# Sheet1.net
KiCad netlist of a schematic drawn in Altium Designer
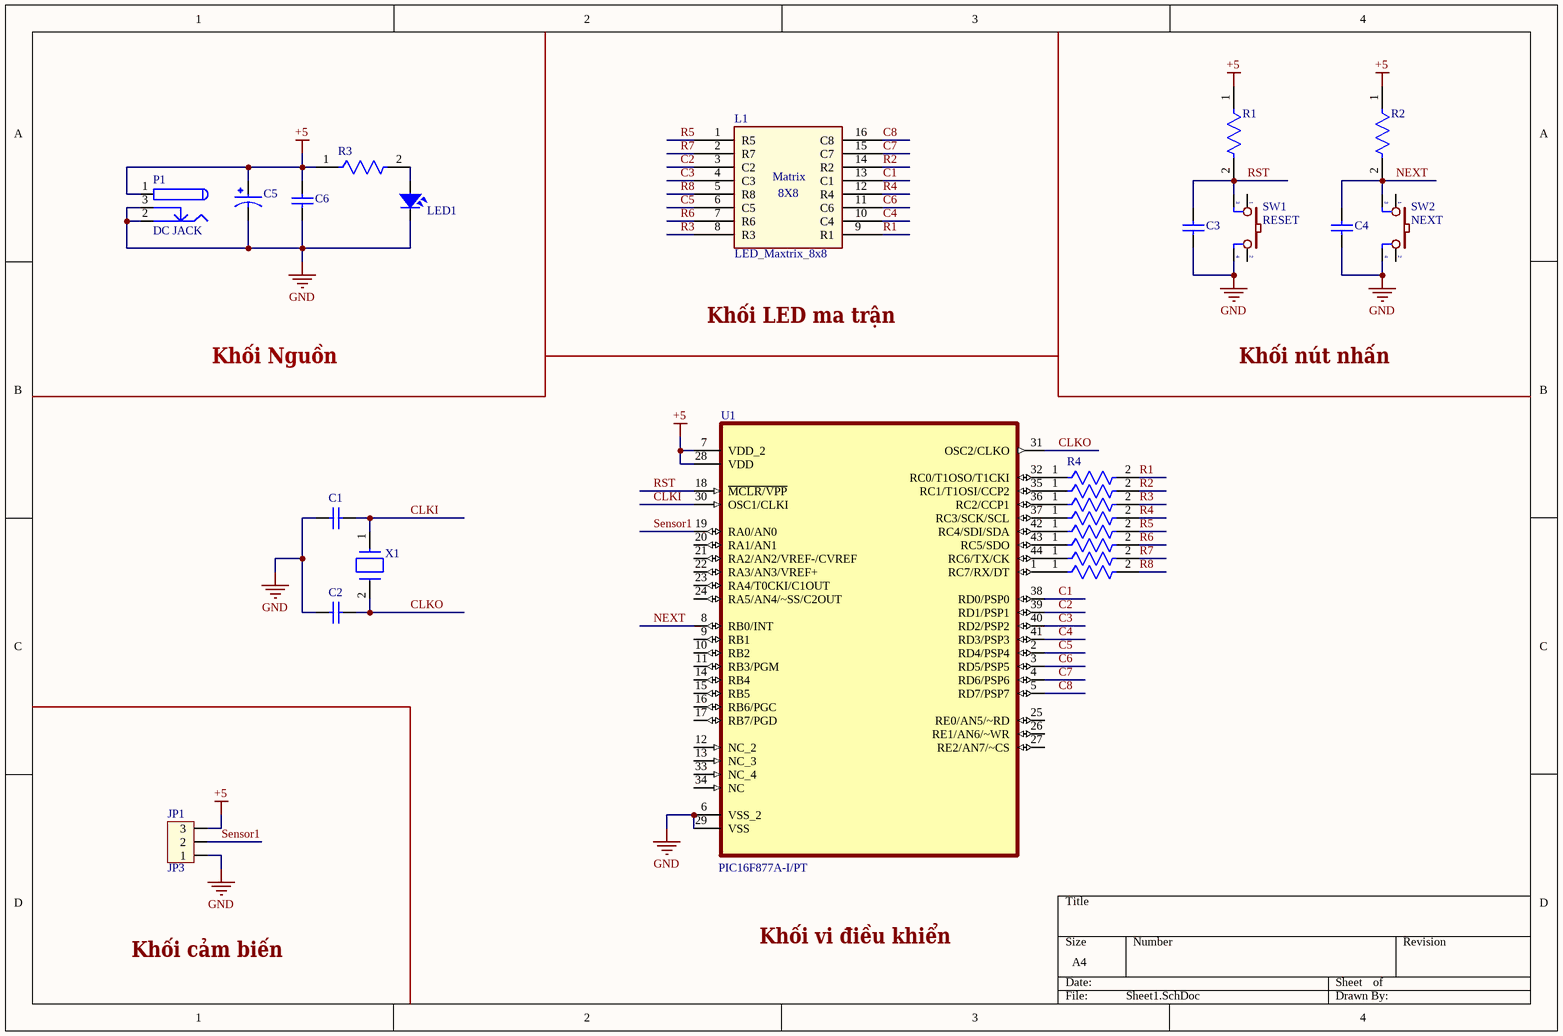
[diagram p0: Sheet1.SchDoc]

(export (version "E")
  (design (tool "Eeschema 10.0.6"))
  (components
    (comp (ref "C1")
      (value "22p")
      (footprint "CAPC2013X94X50LL25T25")
      (description "Cap Ceramic 0.1uF 100V X7R 10% SMD 0805 125°C Embossed T/R")
      (fields
        (field (name "MANUFACTURER") "Kyocera AVX")
        (field (name "MANUFACTURER PART NUMBER") "LD051C104KAB2A")
      )
      (libsource (lib "Lib_BookTS") (part "LD051C104KAB2A"))
    )
    (comp (ref "C2")
      (value "22p")
      (footprint "CAPC2013X94X50LL25T25")
      (description "Cap Ceramic 0.1uF 100V X7R 10% SMD 0805 125°C Embossed T/R")
      (fields
        (field (name "MANUFACTURER") "Kyocera AVX")
        (field (name "MANUFACTURER PART NUMBER") "LD051C104KAB2A")
      )
      (libsource (lib "Lib_BookTS") (part "LD051C104KAB2A"))
    )
    (comp (ref "C3")
      (value "0.1uF")
      (footprint "CAPC2013X94X50LL25T25")
      (description "Cap Ceramic 0.1uF 100V X7R 10% SMD 0805 125°C Embossed T/R")
      (fields
        (field (name "MANUFACTURER") "Kyocera AVX")
        (field (name "MANUFACTURER PART NUMBER") "LD051C104KAB2A")
      )
      (libsource (lib "Lib_BookTS") (part "LD051C104KAB2A"))
    )
    (comp (ref "C4")
      (value "0.1uF")
      (footprint "CAPC2013X94X50LL25T25")
      (description "Cap Ceramic 0.1uF 100V X7R 10% SMD 0805 125°C Embossed T/R")
      (fields
        (field (name "MANUFACTURER") "Kyocera AVX")
        (field (name "MANUFACTURER PART NUMBER") "LD051C104KAB2A")
      )
      (libsource (lib "Lib_BookTS") (part "LD051C104KAB2A"))
    )
    (comp (ref "C5")
      (value "EEE-FK1H101GP")
      (footprint "FP-FKF-MFG")
      (description "Cap Aluminum 100uF 50V 20% (8 X 10.2mm) SMD 350mA 5000 hr 105°C T/R")
      (fields (field (name "MANUFACTURER") "Panasonic") (field (name "TOLERANCE") "20%"))
      (libsource (lib "Lib_BookTS") (part "EEE-FK1H101GP"))
    )
    (comp (ref "C6")
      (value "0.1uF")
      (footprint "CAPC2013X94X50LL25T25")
      (description "Cap Ceramic 0.1uF 100V X7R 10% SMD 0805 125°C Embossed T/R")
      (fields
        (field (name "MANUFACTURER") "Kyocera AVX")
        (field (name "MANUFACTURER PART NUMBER") "LD051C104KAB2A")
      )
      (libsource (lib "Lib_BookTS") (part "LD051C104KAB2A"))
    )
    (comp (ref "JP1")
      (value "JP3")
      (footprint "CON3")
      (description "Connector 3")
      (libsource (lib "Lib_BookTS") (part "Con3"))
    )
    (comp (ref "L1")
      (value "LED_Maxtrix_8x8")
      (footprint "LED_Matrix_8x8")
      (libsource (lib "Lib_BookTS") (part "LED_Maxtrix_8x8"))
    )
    (comp (ref "LED1")
      (value "LED SMD")
      (footprint "SM-LED-0805-Green")
      (libsource (lib "Lib_BookTS") (part "LED-SMD-0805"))
    )
    (comp (ref "P1")
      (value "DC JACK")
      (footprint "DC5.5/2.1")
      (description "Low Voltage Power Supply Connector")
      (libsource (lib "Lib_BookTS") (part "DC5.5/2.1"))
    )
    (comp (ref "R1")
      (value "10k")
      (footprint "FP-CR0805-MFG")
      (description "Res Thick Film 0805 330 Ohm 5% 1/8W ±200ppm/°C Molded SMD SMD Paper Tape on Plastic Reel")
      (fields
        (field (name "MANUFACTURER") "Bourns")
        (field (name "MANUFACTURER PART NUMBER") "CR0805-JW-331ELF")
      )
      (libsource (lib "Lib_BookTS") (part "CR0805-JW-331ELF"))
    )
    (comp (ref "R2")
      (value "10k")
      (footprint "FP-CR0805-MFG")
      (description "Res Thick Film 0805 330 Ohm 5% 1/8W ±200ppm/°C Molded SMD SMD Paper Tape on Plastic Reel")
      (fields
        (field (name "MANUFACTURER") "Bourns")
        (field (name "MANUFACTURER PART NUMBER") "CR0805-JW-331ELF")
      )
      (libsource (lib "Lib_BookTS") (part "CR0805-JW-331ELF"))
    )
    (comp (ref "R3")
      (value "470R")
      (footprint "FP-CR0805-IPC_A")
      (description "Res Thick Film 0805 330 Ohm 5% 1/8W ±200ppm/°C Molded SMD SMD Paper Tape on Plastic Reel")
      (fields
        (field (name "MANUFACTURER") "Bourns")
        (field (name "MANUFACTURER PART NUMBER") "CR0805-JW-331ELF")
      )
      (libsource (lib "Lib_BookTS") (part "CR0805-JW-331ELF"))
    )
    (comp (ref "R4")
      (value "330R")
      (footprint "FP-CR0805-IPC_A")
      (description "Res Thick Film 0805 330 Ohm 5% 1/8W ±200ppm/°C Molded SMD SMD Paper Tape on Plastic Reel")
      (fields
        (field (name "MANUFACTURER") "Bourns")
        (field (name "MANUFACTURER PART NUMBER") "CR0805-JW-331ELF")
      )
      (libsource (lib "Lib_BookTS") (part "CR0805-JW-331ELF"))
    )
    (comp (ref "R5")
      (value "330R")
      (footprint "FP-CR0805-IPC_A")
      (description "Res Thick Film 0805 330 Ohm 5% 1/8W ±200ppm/°C Molded SMD SMD Paper Tape on Plastic Reel")
      (fields
        (field (name "MANUFACTURER") "Bourns")
        (field (name "MANUFACTURER PART NUMBER") "CR0805-JW-331ELF")
      )
      (libsource (lib "Lib_BookTS") (part "CR0805-JW-331ELF"))
    )
    (comp (ref "R6")
      (value "330R")
      (footprint "FP-CR0805-IPC_A")
      (description "Res Thick Film 0805 330 Ohm 5% 1/8W ±200ppm/°C Molded SMD SMD Paper Tape on Plastic Reel")
      (fields
        (field (name "MANUFACTURER") "Bourns")
        (field (name "MANUFACTURER PART NUMBER") "CR0805-JW-331ELF")
      )
      (libsource (lib "Lib_BookTS") (part "CR0805-JW-331ELF"))
    )
    (comp (ref "R7")
      (value "330R")
      (footprint "FP-CR0805-IPC_A")
      (description "Res Thick Film 0805 330 Ohm 5% 1/8W ±200ppm/°C Molded SMD SMD Paper Tape on Plastic Reel")
      (fields
        (field (name "MANUFACTURER") "Bourns")
        (field (name "MANUFACTURER PART NUMBER") "CR0805-JW-331ELF")
      )
      (libsource (lib "Lib_BookTS") (part "CR0805-JW-331ELF"))
    )
    (comp (ref "R8")
      (value "330R")
      (footprint "FP-CR0805-IPC_A")
      (description "Res Thick Film 0805 330 Ohm 5% 1/8W ±200ppm/°C Molded SMD SMD Paper Tape on Plastic Reel")
      (fields
        (field (name "MANUFACTURER") "Bourns")
        (field (name "MANUFACTURER PART NUMBER") "CR0805-JW-331ELF")
      )
      (libsource (lib "Lib_BookTS") (part "CR0805-JW-331ELF"))
    )
    (comp (ref "R9")
      (value "330R")
      (footprint "FP-CR0805-IPC_A")
      (description "Res Thick Film 0805 330 Ohm 5% 1/8W ±200ppm/°C Molded SMD SMD Paper Tape on Plastic Reel")
      (fields
        (field (name "MANUFACTURER") "Bourns")
        (field (name "MANUFACTURER PART NUMBER") "CR0805-JW-331ELF")
      )
      (libsource (lib "Lib_BookTS") (part "CR0805-JW-331ELF"))
    )
    (comp (ref "R10")
      (value "330R")
      (footprint "FP-CR0805-IPC_A")
      (description "Res Thick Film 0805 330 Ohm 5% 1/8W ±200ppm/°C Molded SMD SMD Paper Tape on Plastic Reel")
      (fields
        (field (name "MANUFACTURER") "Bourns")
        (field (name "MANUFACTURER PART NUMBER") "CR0805-JW-331ELF")
      )
      (libsource (lib "Lib_BookTS") (part "CR0805-JW-331ELF"))
    )
    (comp (ref "R11")
      (value "330R")
      (footprint "FP-CR0805-IPC_A")
      (description "Res Thick Film 0805 330 Ohm 5% 1/8W ±200ppm/°C Molded SMD SMD Paper Tape on Plastic Reel")
      (fields
        (field (name "MANUFACTURER") "Bourns")
        (field (name "MANUFACTURER PART NUMBER") "CR0805-JW-331ELF")
      )
      (libsource (lib "Lib_BookTS") (part "CR0805-JW-331ELF"))
    )
    (comp (ref "SW1")
      (value "RESET")
      (footprint "SW4")
      (description "Switch button 4 pin")
      (libsource (lib "Lib_BookTS") (part "SW4-1"))
    )
    (comp (ref "SW2")
      (value "NEXT")
      (footprint "SW4")
      (description "Switch button 4 pin")
      (libsource (lib "Lib_BookTS") (part "SW4-1"))
    )
    (comp (ref "U1")
      (value "PIC16F877A-I/PT")
      (footprint "TQFP-44")
      (description "PIC16F877A Microcontroller IC 8-Bit 20MHz 14KB _8K x 14_ FLASH 44-TQFP _10x10_")
      (fields (field (name "MF") "Microchip"))
      (libsource (lib "Lib_BookTS") (part "PIC16F877A-I/PT"))
    )
    (comp (ref "X1")
      (value "16MHz")
      (footprint "FP-ABM7-MFG")
      (description "Crystal 16MHz ±30ppm (Tol) ±50ppm (Stability) 18pF FUND 50Ohm 2-Pin Mini-CSMD T/R")
      (fields
        (field (name "MANUFACTURER") "Abracon")
        (field (name "MANUFACTURER PART NUMBER") "ABM7-16.000MHZ-4-T")
      )
      (libsource (lib "Lib_BookTS") (part "ABM7-16.000MHZ-4-T"))
    )
  )
  (nets
    (net (code "1") (name "+5") (class "Default")
      (node (ref "C5") (pin "1") (pinfunction "1_1") (pintype "passive"))
      (node (ref "C6") (pin "2") (pinfunction "2_2") (pintype "passive"))
      (node (ref "JP1") (pin "3") (pinfunction "3_3") (pintype "passive"))
      (node (ref "P1") (pin "1") (pinfunction "1_1") (pintype "power_in"))
      (node (ref "R1") (pin "1") (pinfunction "1_1") (pintype "passive"))
      (node (ref "R2") (pin "1") (pinfunction "1_1") (pintype "passive"))
      (node (ref "R3") (pin "1") (pinfunction "1_1") (pintype "passive"))
      (node (ref "U1") (pin "28") (pinfunction "VDD_28") (pintype "power_in"))
      (node (ref "U1") (pin "7") (pinfunction "VDD_2_7") (pintype "power_in"))
    )
    (net (code "2") (name "/C1") (class "Default")
      (node (ref "L1") (pin "13") (pinfunction "C1_13") (pintype "passive"))
      (node (ref "U1") (pin "38") (pinfunction "RD0/PSP0_38") (pintype "bidirectional"))
    )
    (net (code "3") (name "/C2") (class "Default")
      (node (ref "L1") (pin "3") (pinfunction "C2_3") (pintype "passive"))
      (node (ref "U1") (pin "39") (pinfunction "RD1/PSP1_39") (pintype "bidirectional"))
    )
    (net (code "4") (name "/C3") (class "Default")
      (node (ref "L1") (pin "4") (pinfunction "C3_4") (pintype "passive"))
      (node (ref "U1") (pin "40") (pinfunction "RD2/PSP2_40") (pintype "bidirectional"))
    )
    (net (code "5") (name "/C4") (class "Default")
      (node (ref "L1") (pin "10") (pinfunction "C4_10") (pintype "passive"))
      (node (ref "U1") (pin "41") (pinfunction "RD3/PSP3_41") (pintype "bidirectional"))
    )
    (net (code "6") (name "/C5") (class "Default")
      (node (ref "L1") (pin "6") (pinfunction "C5_6") (pintype "passive"))
      (node (ref "U1") (pin "2") (pinfunction "RD4/PSP4_2") (pintype "bidirectional"))
    )
    (net (code "7") (name "/C6") (class "Default")
      (node (ref "L1") (pin "11") (pinfunction "C6_11") (pintype "passive"))
      (node (ref "U1") (pin "3") (pinfunction "RD5/PSP5_3") (pintype "bidirectional"))
    )
    (net (code "8") (name "/C7") (class "Default")
      (node (ref "L1") (pin "15") (pinfunction "C7_15") (pintype "passive"))
      (node (ref "U1") (pin "4") (pinfunction "RD6/PSP6_4") (pintype "bidirectional"))
    )
    (net (code "9") (name "/C8") (class "Default")
      (node (ref "L1") (pin "16") (pinfunction "C8_16") (pintype "passive"))
      (node (ref "U1") (pin "5") (pinfunction "RD7/PSP7_5") (pintype "bidirectional"))
    )
    (net (code "10") (name "/CLKI") (class "Default")
      (node (ref "C1") (pin "2") (pinfunction "2_2") (pintype "passive"))
      (node (ref "U1") (pin "30") (pinfunction "OSC1/CLKI_30") (pintype "input"))
      (node (ref "X1") (pin "1") (pinfunction "1_1") (pintype "passive"))
    )
    (net (code "11") (name "/CLKO") (class "Default")
      (node (ref "C2") (pin "2") (pinfunction "2_2") (pintype "passive"))
      (node (ref "U1") (pin "31") (pinfunction "OSC2/CLKO_31") (pintype "output"))
      (node (ref "X1") (pin "2") (pinfunction "2_2") (pintype "passive"))
    )
    (net (code "16") (name "/NEXT") (class "Default")
      (node (ref "C4") (pin "2") (pinfunction "2_2") (pintype "passive"))
      (node (ref "R2") (pin "2") (pinfunction "2_2") (pintype "passive"))
      (node (ref "SW2") (pin "3") (pinfunction "3_3") (pintype "passive"))
      (node (ref "U1") (pin "8") (pinfunction "RB0/INT_8") (pintype "bidirectional"))
    )
    (net (code "17") (name "/R1") (class "Default")
      (node (ref "L1") (pin "9") (pinfunction "R1_9") (pintype "passive"))
      (node (ref "R4") (pin "2") (pinfunction "2_2") (pintype "passive"))
    )
    (net (code "18") (name "/R2") (class "Default")
      (node (ref "L1") (pin "14") (pinfunction "R2_14") (pintype "passive"))
      (node (ref "R5") (pin "2") (pinfunction "2_2") (pintype "passive"))
    )
    (net (code "19") (name "/R3") (class "Default")
      (node (ref "L1") (pin "8") (pinfunction "R3_8") (pintype "passive"))
      (node (ref "R6") (pin "2") (pinfunction "2_2") (pintype "passive"))
    )
    (net (code "20") (name "/R4") (class "Default")
      (node (ref "L1") (pin "12") (pinfunction "R4_12") (pintype "passive"))
      (node (ref "R7") (pin "2") (pinfunction "2_2") (pintype "passive"))
    )
    (net (code "21") (name "/R5") (class "Default")
      (node (ref "L1") (pin "1") (pinfunction "R5_1") (pintype "passive"))
      (node (ref "R8") (pin "2") (pinfunction "2_2") (pintype "passive"))
    )
    (net (code "22") (name "/R6") (class "Default")
      (node (ref "L1") (pin "7") (pinfunction "R6_7") (pintype "passive"))
      (node (ref "R9") (pin "2") (pinfunction "2_2") (pintype "passive"))
    )
    (net (code "23") (name "/R7") (class "Default")
      (node (ref "L1") (pin "2") (pinfunction "R7_2") (pintype "passive"))
      (node (ref "R10") (pin "2") (pinfunction "2_2") (pintype "passive"))
    )
    (net (code "24") (name "/R8") (class "Default")
      (node (ref "L1") (pin "5") (pinfunction "R8_5") (pintype "passive"))
      (node (ref "R11") (pin "2") (pinfunction "2_2") (pintype "passive"))
    )
    (net (code "25") (name "/RST") (class "Default")
      (node (ref "C3") (pin "2") (pinfunction "2_2") (pintype "passive"))
      (node (ref "R1") (pin "2") (pinfunction "2_2") (pintype "passive"))
      (node (ref "SW1") (pin "3") (pinfunction "3_3") (pintype "passive"))
      (node (ref "U1") (pin "18") (pinfunction "~{MCLR/VPP}_18") (pintype "input"))
    )
    (net (code "26") (name "/Sensor1") (class "Default")
      (node (ref "JP1") (pin "2") (pinfunction "2_2") (pintype "passive"))
      (node (ref "U1") (pin "19") (pinfunction "RA0/AN0_19") (pintype "bidirectional"))
    )
    (net (code "27") (name "GND") (class "Default")
      (node (ref "C1") (pin "1") (pinfunction "1_1") (pintype "passive"))
      (node (ref "C2") (pin "1") (pinfunction "1_1") (pintype "passive"))
      (node (ref "C3") (pin "1") (pinfunction "1_1") (pintype "passive"))
      (node (ref "C4") (pin "1") (pinfunction "1_1") (pintype "passive"))
      (node (ref "C5") (pin "2") (pinfunction "2_2") (pintype "passive"))
      (node (ref "C6") (pin "1") (pinfunction "1_1") (pintype "passive"))
      (node (ref "JP1") (pin "1") (pinfunction "1_1") (pintype "passive"))
      (node (ref "LED1") (pin "2") (pinfunction "2_2") (pintype "passive"))
      (node (ref "P1") (pin "2") (pinfunction "2_2") (pintype "power_in"))
      (node (ref "P1") (pin "3") (pinfunction "3_3") (pintype "power_in"))
      (node (ref "SW1") (pin "4") (pinfunction "4_4") (pintype "passive"))
      (node (ref "SW2") (pin "4") (pinfunction "4_4") (pintype "passive"))
      (node (ref "U1") (pin "29") (pinfunction "VSS_29") (pintype "power_in"))
      (node (ref "U1") (pin "6") (pinfunction "VSS_2_6") (pintype "power_in"))
    )
    (net (code "28") (name "Net-(LED1-Pad1)") (class "Default")
      (node (ref "LED1") (pin "1") (pinfunction "1_1") (pintype "passive"))
      (node (ref "R3") (pin "2") (pinfunction "2_2") (pintype "passive"))
    )
    (net (code "29") (name "Net-(U1-RC0{slash}T1OSO{slash}T1CKI)") (class "Default")
      (node (ref "R4") (pin "1") (pinfunction "1_1") (pintype "passive"))
      (node (ref "U1") (pin "32") (pinfunction "RC0/T1OSO/T1CKI_32") (pintype "bidirectional"))
    )
    (net (code "30") (name "Net-(U1-RC1{slash}T1OSI{slash}CCP2)") (class "Default")
      (node (ref "R5") (pin "1") (pinfunction "1_1") (pintype "passive"))
      (node (ref "U1") (pin "35") (pinfunction "RC1/T1OSI/CCP2_35") (pintype "bidirectional"))
    )
    (net (code "31") (name "Net-(U1-RC2{slash}CCP1)") (class "Default")
      (node (ref "R6") (pin "1") (pinfunction "1_1") (pintype "passive"))
      (node (ref "U1") (pin "36") (pinfunction "RC2/CCP1_36") (pintype "bidirectional"))
    )
    (net (code "32") (name "Net-(U1-RC3{slash}SCK{slash}SCL)") (class "Default")
      (node (ref "R7") (pin "1") (pinfunction "1_1") (pintype "passive"))
      (node (ref "U1") (pin "37") (pinfunction "RC3/SCK/SCL_37") (pintype "bidirectional"))
    )
    (net (code "33") (name "Net-(U1-RC4{slash}SDI{slash}SDA)") (class "Default")
      (node (ref "R8") (pin "1") (pinfunction "1_1") (pintype "passive"))
      (node (ref "U1") (pin "42") (pinfunction "RC4/SDI/SDA_42") (pintype "bidirectional"))
    )
    (net (code "34") (name "Net-(U1-RC5{slash}SDO)") (class "Default")
      (node (ref "R9") (pin "1") (pinfunction "1_1") (pintype "passive"))
      (node (ref "U1") (pin "43") (pinfunction "RC5/SDO_43") (pintype "bidirectional"))
    )
    (net (code "35") (name "Net-(U1-RC6{slash}TX{slash}CK)") (class "Default")
      (node (ref "R10") (pin "1") (pinfunction "1_1") (pintype "passive"))
      (node (ref "U1") (pin "44") (pinfunction "RC6/TX/CK_44") (pintype "bidirectional"))
    )
    (net (code "36") (name "Net-(U1-RC7{slash}RX{slash}DT)") (class "Default")
      (node (ref "R11") (pin "1") (pinfunction "1_1") (pintype "passive"))
      (node (ref "U1") (pin "1") (pinfunction "RC7/RX/DT_1") (pintype "bidirectional"))
    )
    (net (code "37") (name "unconnected-(SW1-Pad1)") (class "Default")
      (node (ref "SW1") (pin "1") (pinfunction "1_1") (pintype "passive"))
    )
    (net (code "38") (name "unconnected-(SW1-Pad2)") (class "Default")
      (node (ref "SW1") (pin "2") (pinfunction "2_2") (pintype "passive"))
    )
    (net (code "39") (name "unconnected-(SW2-Pad1)") (class "Default")
      (node (ref "SW2") (pin "1") (pinfunction "1_1") (pintype "passive"))
    )
    (net (code "40") (name "unconnected-(SW2-Pad2)") (class "Default")
      (node (ref "SW2") (pin "2") (pinfunction "2_2") (pintype "passive"))
    )
    (net (code "41") (name "unconnected-(U1-NC-Pad34)") (class "Default")
      (node (ref "U1") (pin "34") (pinfunction "NC_34") (pintype "input"))
    )
    (net (code "42") (name "unconnected-(U1-NC_2-Pad12)") (class "Default")
      (node (ref "U1") (pin "12") (pinfunction "NC_2_12") (pintype "input"))
    )
    (net (code "43") (name "unconnected-(U1-NC_3-Pad13)") (class "Default")
      (node (ref "U1") (pin "13") (pinfunction "NC_3_13") (pintype "input"))
    )
    (net (code "44") (name "unconnected-(U1-NC_4-Pad33)") (class "Default")
      (node (ref "U1") (pin "33") (pinfunction "NC_4_33") (pintype "input"))
    )
    (net (code "45") (name "unconnected-(U1-RA1{slash}AN1-Pad20)") (class "Default")
      (node (ref "U1") (pin "20") (pinfunction "RA1/AN1_20") (pintype "bidirectional"))
    )
    (net (code "46") (name "unconnected-(U1-RA2{slash}AN2{slash}VREF-{slash}CVREF-Pad21)") (class "Default")
      (node (ref "U1") (pin "21") (pinfunction "RA2/AN2/VREF-/CVREF_21") (pintype "bidirectional"))
    )
    (net (code "47") (name "unconnected-(U1-RA3{slash}AN3{slash}VREF+-Pad22)") (class "Default")
      (node (ref "U1") (pin "22") (pinfunction "RA3/AN3/VREF+_22") (pintype "bidirectional"))
    )
    (net (code "48") (name "unconnected-(U1-RA4{slash}T0CKI{slash}C1OUT-Pad23)") (class "Default")
      (node (ref "U1") (pin "23") (pinfunction "RA4/T0CKI/C1OUT_23") (pintype "bidirectional"))
    )
    (net (code "49") (name "unconnected-(U1-RA5{slash}AN4{slash}~SS{slash}C2OUT-Pad24)") (class "Default")
      (node (ref "U1") (pin "24") (pinfunction "RA5/AN4/~SS/C2OUT_24") (pintype "bidirectional"))
    )
    (net (code "50") (name "unconnected-(U1-RB1-Pad9)") (class "Default")
      (node (ref "U1") (pin "9") (pinfunction "RB1_9") (pintype "bidirectional"))
    )
    (net (code "51") (name "unconnected-(U1-RB2-Pad10)") (class "Default")
      (node (ref "U1") (pin "10") (pinfunction "RB2_10") (pintype "bidirectional"))
    )
    (net (code "52") (name "unconnected-(U1-RB3{slash}PGM-Pad11)") (class "Default")
      (node (ref "U1") (pin "11") (pinfunction "RB3/PGM_11") (pintype "bidirectional"))
    )
    (net (code "53") (name "unconnected-(U1-RB4-Pad14)") (class "Default")
      (node (ref "U1") (pin "14") (pinfunction "RB4_14") (pintype "bidirectional"))
    )
    (net (code "54") (name "unconnected-(U1-RB5-Pad15)") (class "Default")
      (node (ref "U1") (pin "15") (pinfunction "RB5_15") (pintype "bidirectional"))
    )
    (net (code "55") (name "unconnected-(U1-RB6{slash}PGC-Pad16)") (class "Default")
      (node (ref "U1") (pin "16") (pinfunction "RB6/PGC_16") (pintype "bidirectional"))
    )
    (net (code "56") (name "unconnected-(U1-RB7{slash}PGD-Pad17)") (class "Default")
      (node (ref "U1") (pin "17") (pinfunction "RB7/PGD_17") (pintype "bidirectional"))
    )
    (net (code "57") (name "unconnected-(U1-RE0{slash}AN5{slash}~RD-Pad25)") (class "Default")
      (node (ref "U1") (pin "25") (pinfunction "RE0/AN5/~RD_25") (pintype "bidirectional"))
    )
    (net (code "58") (name "unconnected-(U1-RE1{slash}AN6{slash}~WR-Pad26)") (class "Default")
      (node (ref "U1") (pin "26") (pinfunction "RE1/AN6/~WR_26") (pintype "bidirectional"))
    )
    (net (code "59") (name "unconnected-(U1-RE2{slash}AN7{slash}~CS-Pad27)") (class "Default")
      (node (ref "U1") (pin "27") (pinfunction "RE2/AN7/~CS_27") (pintype "bidirectional"))
    )
  )
)
